# Sitara_IO_Bank_123.net
KiCad netlist of a schematic drawn in Altium Designer
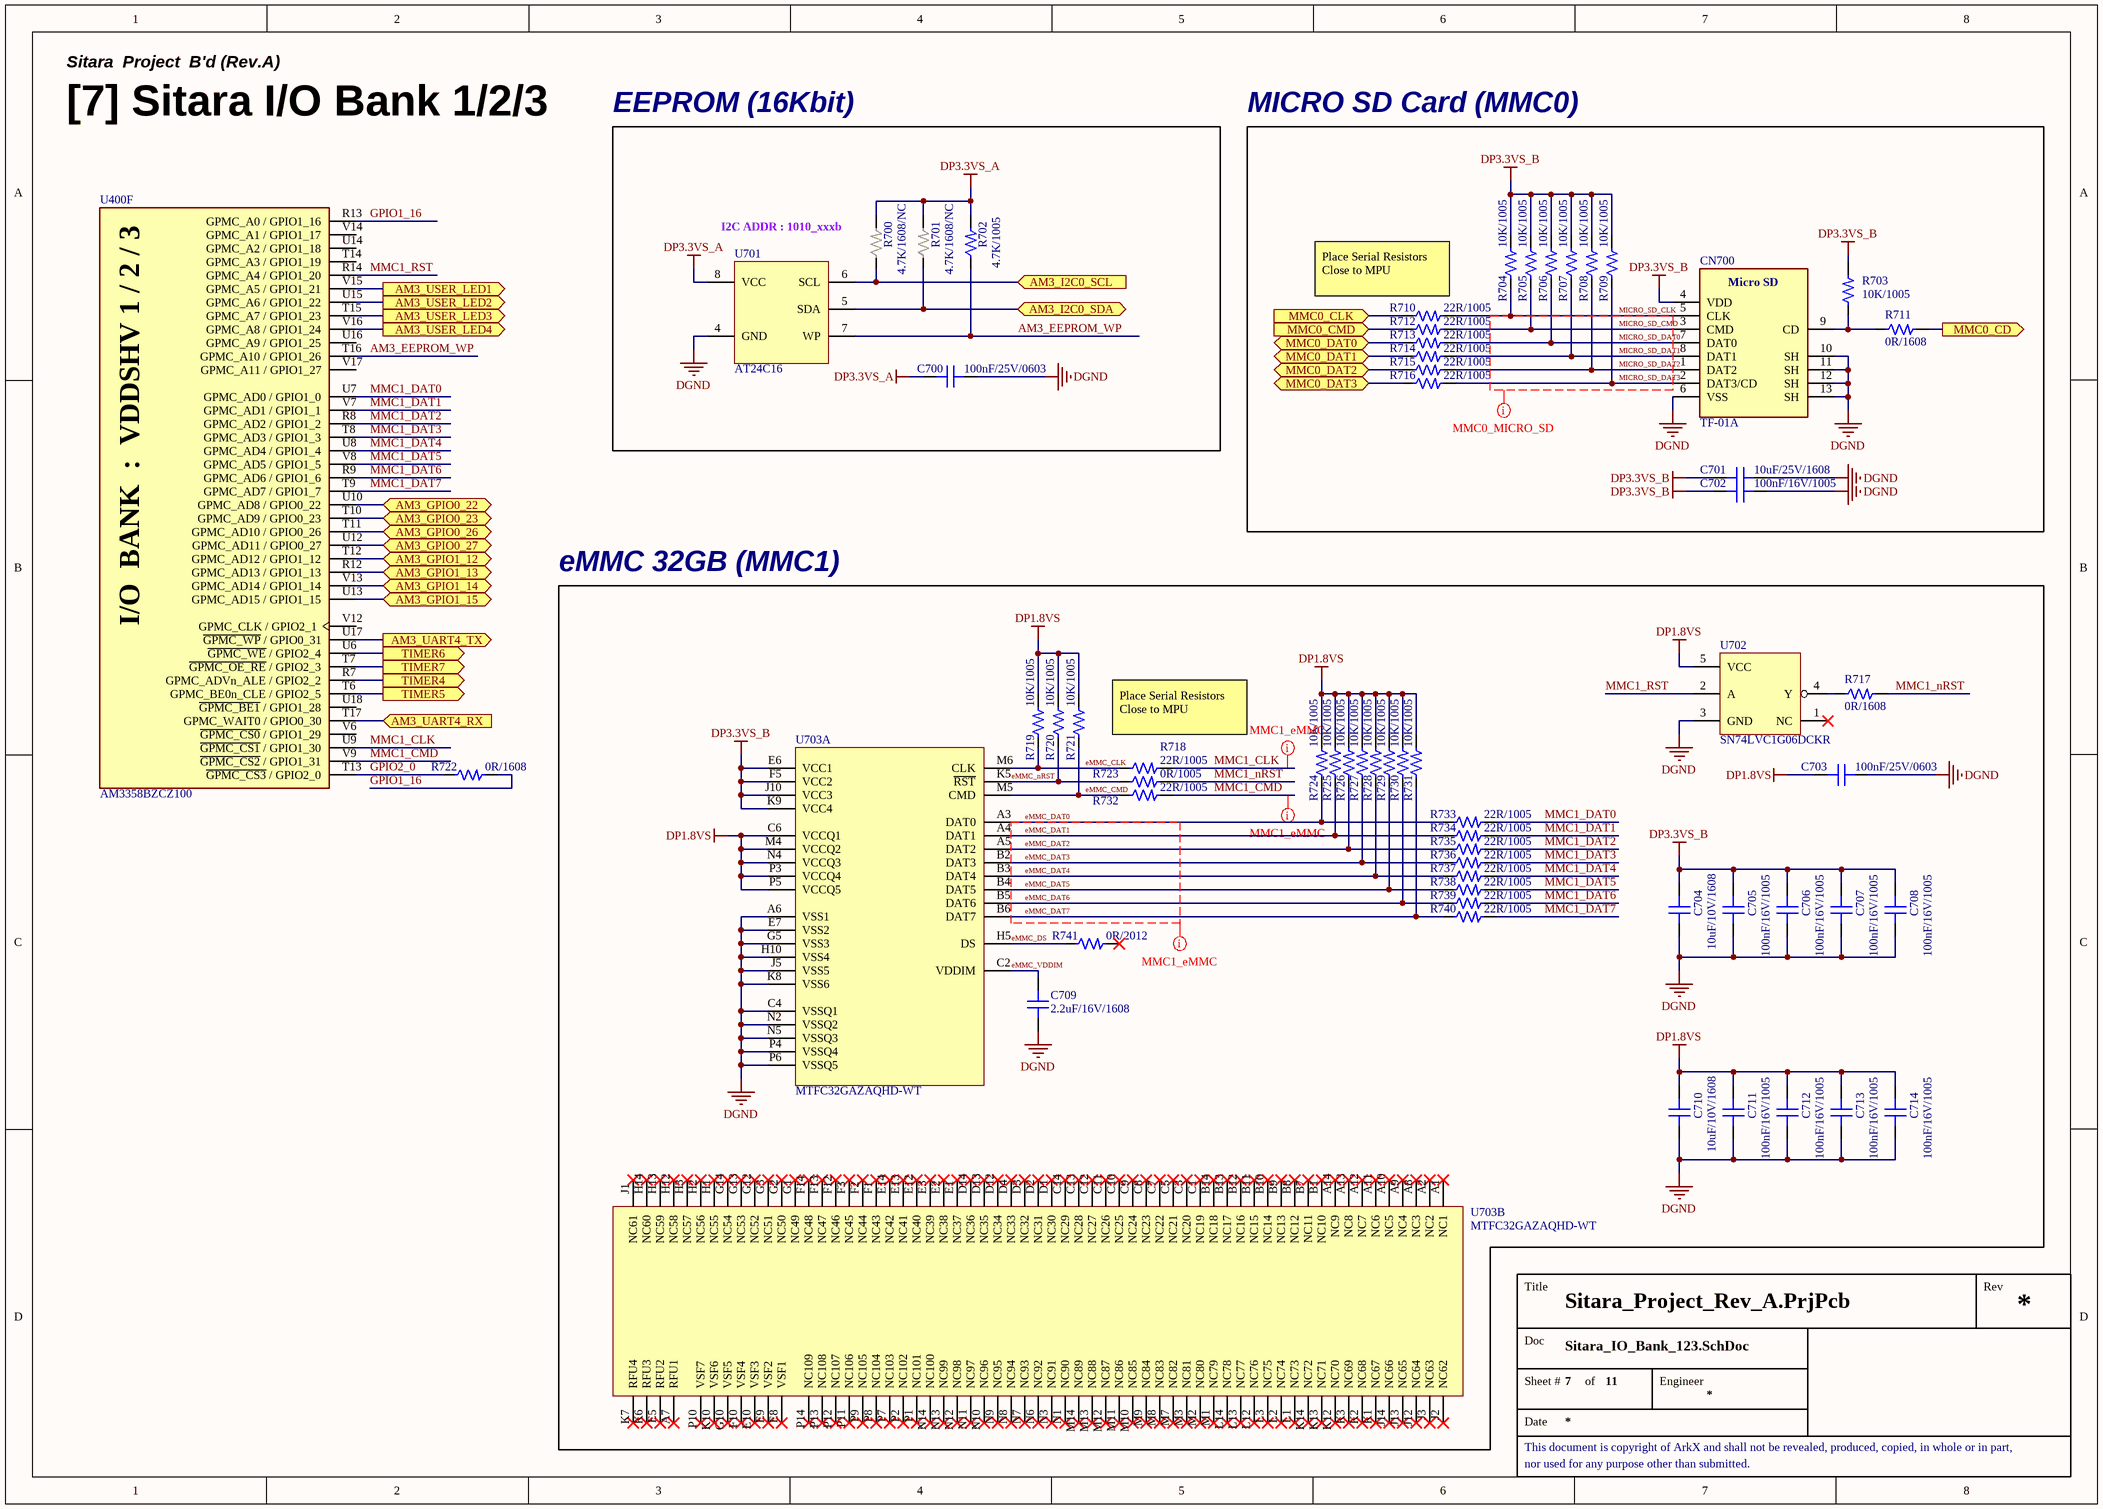
[diagram p0: Sitara_IO_Bank_123.SchDoc]

(export (version "E")
  (design (tool "Eeschema 10.0.6"))
  (components
    (comp (ref "C700")
      (value "100nF/25V/0603")
      (footprint "CAP 0603 (0201_INCH)")
      (description "Ceramic CAP_100nF/25V/0603")
      (fields (field (name "LCSC PART #") "C181047"))
      (libsource (lib "Arkx") (part "CAP_100nF/25V/0603"))
    )
    (comp (ref "C701")
      (value "10uF/25V/1608")
      (footprint "CAP 1608 (0603_INCH)")
      (description "Ceramic CAP_10uF/25V/1608")
      (fields (field (name "LCSC PART #") "C96446"))
      (libsource (lib "Arkx") (part "CAP_10uF/25V/1608"))
    )
    (comp (ref "C702")
      (value "100nF/16V/1005")
      (footprint "CAP 1005 (0402_INCH)")
      (description "Ceramic CAP_100nF/16V/1005")
      (fields (field (name "LCSC PART #") "C1525"))
      (libsource (lib "Arkx") (part "CAP_100nF/16V/1005"))
    )
    (comp (ref "C703")
      (value "100nF/25V/0603")
      (footprint "CAP 0603 (0201_INCH)")
      (description "Ceramic CAP_100nF/25V/0603")
      (fields (field (name "LCSC PART #") "C181047"))
      (libsource (lib "Arkx") (part "CAP_100nF/25V/0603"))
    )
    (comp (ref "C704")
      (value "10uF/10V/1608")
      (footprint "CAP 1608 (0603_INCH)")
      (description "Ceramic CAP_10uF/10V/1608")
      (fields (field (name "LCSC PART #") "C19702"))
      (libsource (lib "Arkx") (part "CAP_10uF/10V/1608"))
    )
    (comp (ref "C705")
      (value "100nF/16V/1005")
      (footprint "CAP 1005 (0402_INCH)")
      (description "Ceramic CAP_100nF/16V/1005")
      (fields (field (name "LCSC PART #") "C1525"))
      (libsource (lib "Arkx") (part "CAP_100nF/16V/1005"))
    )
    (comp (ref "C706")
      (value "100nF/16V/1005")
      (footprint "CAP 1005 (0402_INCH)")
      (description "Ceramic CAP_100nF/16V/1005")
      (fields (field (name "LCSC PART #") "C1525"))
      (libsource (lib "Arkx") (part "CAP_100nF/16V/1005"))
    )
    (comp (ref "C707")
      (value "100nF/16V/1005")
      (footprint "CAP 1005 (0402_INCH)")
      (description "Ceramic CAP_100nF/16V/1005")
      (fields (field (name "LCSC PART #") "C1525"))
      (libsource (lib "Arkx") (part "CAP_100nF/16V/1005"))
    )
    (comp (ref "C708")
      (value "100nF/16V/1005")
      (footprint "CAP 1005 (0402_INCH)")
      (description "Ceramic CAP_100nF/16V/1005")
      (fields (field (name "LCSC PART #") "C1525"))
      (libsource (lib "Arkx") (part "CAP_100nF/16V/1005"))
    )
    (comp (ref "C709")
      (value "2.2uF/16V/1608")
      (footprint "CAP 1608 (0603_INCH)")
      (description "Ceramic CAP_2.2uF/16V/1608")
      (fields (field (name "LCSC PART #") "C23630"))
      (libsource (lib "Arkx") (part "CAP_2.2uF/16V/1608"))
    )
    (comp (ref "C710")
      (value "10uF/10V/1608")
      (footprint "CAP 1608 (0603_INCH)")
      (description "Ceramic CAP_10uF/10V/1608")
      (fields (field (name "LCSC PART #") "C19702"))
      (libsource (lib "Arkx") (part "CAP_10uF/10V/1608"))
    )
    (comp (ref "C711")
      (value "100nF/16V/1005")
      (footprint "CAP 1005 (0402_INCH)")
      (description "Ceramic CAP_100nF/16V/1005")
      (fields (field (name "LCSC PART #") "C1525"))
      (libsource (lib "Arkx") (part "CAP_100nF/16V/1005"))
    )
    (comp (ref "C712")
      (value "100nF/16V/1005")
      (footprint "CAP 1005 (0402_INCH)")
      (description "Ceramic CAP_100nF/16V/1005")
      (fields (field (name "LCSC PART #") "C1525"))
      (libsource (lib "Arkx") (part "CAP_100nF/16V/1005"))
    )
    (comp (ref "C713")
      (value "100nF/16V/1005")
      (footprint "CAP 1005 (0402_INCH)")
      (description "Ceramic CAP_100nF/16V/1005")
      (fields (field (name "LCSC PART #") "C1525"))
      (libsource (lib "Arkx") (part "CAP_100nF/16V/1005"))
    )
    (comp (ref "C714")
      (value "100nF/16V/1005")
      (footprint "CAP 1005 (0402_INCH)")
      (description "Ceramic CAP_100nF/16V/1005")
      (fields (field (name "LCSC PART #") "C1525"))
      (libsource (lib "Arkx") (part "CAP_100nF/16V/1005"))
    )
    (comp (ref "CN700")
      (value "TF-01A")
      (footprint "CON_MICRO-SD_Socket_TF-01A")
      (description "Card Slot MicroSD card (TF card) Self-bouncing SMD SD Card / Memory Card Connector ROHS")
      (fields (field (name "LCSC PART #") "C91145"))
      (libsource (lib "Arkx") (part "CON_MICRO-SD_Socket_TF-01A"))
    )
    (comp (ref "R700")
      (value "4.7K/1608/NC")
      (footprint "RES 1608 (0603_inch)/NC")
      (description "RES_4.7K/1608/0.1W")
      (libsource (lib "Arkx") (part "RES_NC_4.7K/1608/0.1W"))
    )
    (comp (ref "R701")
      (value "4.7K/1608/NC")
      (footprint "RES 1608 (0603_inch)/NC")
      (description "RES_4.7K/1608/0.1W")
      (libsource (lib "Arkx") (part "RES_NC_4.7K/1608/0.1W"))
    )
    (comp (ref "R702")
      (value "4.7K/1005")
      (footprint "RES 1005 (0402_inch)")
      (description "RES_4.7K/1005/62.5mW")
      (fields (field (name "LCSC PART #") "C25900"))
      (libsource (lib "Arkx") (part "RES_4.7K/1005/62.5mW"))
    )
    (comp (ref "R703")
      (value "10K/1005")
      (footprint "RES 1005 (0402_inch)")
      (description "RES_10K/1005/62.5mW")
      (fields (field (name "LCSC PART #") "C25744"))
      (libsource (lib "Arkx") (part "RES_10K/1005/62.5mW"))
    )
    (comp (ref "R704")
      (value "10K/1005")
      (footprint "RES 1005 (0402_inch)")
      (description "RES_10K/1005/62.5mW")
      (fields (field (name "LCSC PART #") "C25744"))
      (libsource (lib "Arkx") (part "RES_10K/1005/62.5mW"))
    )
    (comp (ref "R705")
      (value "10K/1005")
      (footprint "RES 1005 (0402_inch)")
      (description "RES_10K/1005/62.5mW")
      (fields (field (name "LCSC PART #") "C25744"))
      (libsource (lib "Arkx") (part "RES_10K/1005/62.5mW"))
    )
    (comp (ref "R706")
      (value "10K/1005")
      (footprint "RES 1005 (0402_inch)")
      (description "RES_10K/1005/62.5mW")
      (fields (field (name "LCSC PART #") "C25744"))
      (libsource (lib "Arkx") (part "RES_10K/1005/62.5mW"))
    )
    (comp (ref "R707")
      (value "10K/1005")
      (footprint "RES 1005 (0402_inch)")
      (description "RES_10K/1005/62.5mW")
      (fields (field (name "LCSC PART #") "C25744"))
      (libsource (lib "Arkx") (part "RES_10K/1005/62.5mW"))
    )
    (comp (ref "R708")
      (value "10K/1005")
      (footprint "RES 1005 (0402_inch)")
      (description "RES_10K/1005/62.5mW")
      (fields (field (name "LCSC PART #") "C25744"))
      (libsource (lib "Arkx") (part "RES_10K/1005/62.5mW"))
    )
    (comp (ref "R709")
      (value "10K/1005")
      (footprint "RES 1005 (0402_inch)")
      (description "RES_10K/1005/62.5mW")
      (fields (field (name "LCSC PART #") "C25744"))
      (libsource (lib "Arkx") (part "RES_10K/1005/62.5mW"))
    )
    (comp (ref "R710")
      (value "22R/1005")
      (footprint "RES 1005 (0402_inch)")
      (description "RES_22R/1005/62.5mW")
      (fields (field (name "LCSC PART #") "C25092"))
      (libsource (lib "Arkx") (part "RES_22R/1005/62.5mW"))
    )
    (comp (ref "R711")
      (value "0R/1608")
      (footprint "RES 1608 (0603_inch)")
      (description "RES_0R/1608/0.1W")
      (fields (field (name "LCSC PART #") "C21189"))
      (libsource (lib "Arkx") (part "RES_0R/1608/0.1W"))
    )
    (comp (ref "R712")
      (value "22R/1005")
      (footprint "RES 1005 (0402_inch)")
      (description "RES_22R/1005/62.5mW")
      (fields (field (name "LCSC PART #") "C25092"))
      (libsource (lib "Arkx") (part "RES_22R/1005/62.5mW"))
    )
    (comp (ref "R713")
      (value "22R/1005")
      (footprint "RES 1005 (0402_inch)")
      (description "RES_22R/1005/62.5mW")
      (fields (field (name "LCSC PART #") "C25092"))
      (libsource (lib "Arkx") (part "RES_22R/1005/62.5mW"))
    )
    (comp (ref "R714")
      (value "22R/1005")
      (footprint "RES 1005 (0402_inch)")
      (description "RES_22R/1005/62.5mW")
      (fields (field (name "LCSC PART #") "C25092"))
      (libsource (lib "Arkx") (part "RES_22R/1005/62.5mW"))
    )
    (comp (ref "R715")
      (value "22R/1005")
      (footprint "RES 1005 (0402_inch)")
      (description "RES_22R/1005/62.5mW")
      (fields (field (name "LCSC PART #") "C25092"))
      (libsource (lib "Arkx") (part "RES_22R/1005/62.5mW"))
    )
    (comp (ref "R716")
      (value "22R/1005")
      (footprint "RES 1005 (0402_inch)")
      (description "RES_22R/1005/62.5mW")
      (fields (field (name "LCSC PART #") "C25092"))
      (libsource (lib "Arkx") (part "RES_22R/1005/62.5mW"))
    )
    (comp (ref "R717")
      (value "0R/1608")
      (footprint "RES 1608 (0603_inch)")
      (description "RES_0R/1608/0.1W")
      (fields (field (name "LCSC PART #") "C21189"))
      (libsource (lib "Arkx") (part "RES_0R/1608/0.1W"))
    )
    (comp (ref "R718")
      (value "22R/1005")
      (footprint "RES 1005 (0402_inch)")
      (description "RES_22R/1005/62.5mW")
      (fields (field (name "LCSC PART #") "C25092"))
      (libsource (lib "Arkx") (part "RES_22R/1005/62.5mW"))
    )
    (comp (ref "R719")
      (value "10K/1005")
      (footprint "RES 1005 (0402_inch)")
      (description "RES_10K/1005/62.5mW")
      (fields (field (name "LCSC PART #") "C25744"))
      (libsource (lib "Arkx") (part "RES_10K/1005/62.5mW"))
    )
    (comp (ref "R720")
      (value "10K/1005")
      (footprint "RES 1005 (0402_inch)")
      (description "RES_10K/1005/62.5mW")
      (fields (field (name "LCSC PART #") "C25744"))
      (libsource (lib "Arkx") (part "RES_10K/1005/62.5mW"))
    )
    (comp (ref "R721")
      (value "10K/1005")
      (footprint "RES 1005 (0402_inch)")
      (description "RES_10K/1005/62.5mW")
      (fields (field (name "LCSC PART #") "C25744"))
      (libsource (lib "Arkx") (part "RES_10K/1005/62.5mW"))
    )
    (comp (ref "R722")
      (value "0R/1608")
      (footprint "RES 1608 (0603_inch)")
      (description "RES_0R/1608/0.1W")
      (fields (field (name "LCSC PART #") "C21189"))
      (libsource (lib "Arkx") (part "RES_0R/1608/0.1W"))
    )
    (comp (ref "R723")
      (value "0R/1005")
      (footprint "RES 1005 (0402_inch)")
      (description "RES_0R/1005/62.5mW")
      (fields (field (name "LCSC PART #") "C17168"))
      (libsource (lib "Arkx") (part "RES_0R/1005/62.5mW"))
    )
    (comp (ref "R724")
      (value "10K/1005")
      (footprint "RES 1005 (0402_inch)")
      (description "RES_10K/1005/62.5mW")
      (fields (field (name "LCSC PART #") "C25744"))
      (libsource (lib "Arkx") (part "RES_10K/1005/62.5mW"))
    )
    (comp (ref "R725")
      (value "10K/1005")
      (footprint "RES 1005 (0402_inch)")
      (description "RES_10K/1005/62.5mW")
      (fields (field (name "LCSC PART #") "C25744"))
      (libsource (lib "Arkx") (part "RES_10K/1005/62.5mW"))
    )
    (comp (ref "R726")
      (value "10K/1005")
      (footprint "RES 1005 (0402_inch)")
      (description "RES_10K/1005/62.5mW")
      (fields (field (name "LCSC PART #") "C25744"))
      (libsource (lib "Arkx") (part "RES_10K/1005/62.5mW"))
    )
    (comp (ref "R727")
      (value "10K/1005")
      (footprint "RES 1005 (0402_inch)")
      (description "RES_10K/1005/62.5mW")
      (fields (field (name "LCSC PART #") "C25744"))
      (libsource (lib "Arkx") (part "RES_10K/1005/62.5mW"))
    )
    (comp (ref "R728")
      (value "10K/1005")
      (footprint "RES 1005 (0402_inch)")
      (description "RES_10K/1005/62.5mW")
      (fields (field (name "LCSC PART #") "C25744"))
      (libsource (lib "Arkx") (part "RES_10K/1005/62.5mW"))
    )
    (comp (ref "R729")
      (value "10K/1005")
      (footprint "RES 1005 (0402_inch)")
      (description "RES_10K/1005/62.5mW")
      (fields (field (name "LCSC PART #") "C25744"))
      (libsource (lib "Arkx") (part "RES_10K/1005/62.5mW"))
    )
    (comp (ref "R730")
      (value "10K/1005")
      (footprint "RES 1005 (0402_inch)")
      (description "RES_10K/1005/62.5mW")
      (fields (field (name "LCSC PART #") "C25744"))
      (libsource (lib "Arkx") (part "RES_10K/1005/62.5mW"))
    )
    (comp (ref "R731")
      (value "10K/1005")
      (footprint "RES 1005 (0402_inch)")
      (description "RES_10K/1005/62.5mW")
      (fields (field (name "LCSC PART #") "C25744"))
      (libsource (lib "Arkx") (part "RES_10K/1005/62.5mW"))
    )
    (comp (ref "R732")
      (value "22R/1005")
      (footprint "RES 1005 (0402_inch)")
      (description "RES_22R/1005/62.5mW")
      (fields (field (name "LCSC PART #") "C25092"))
      (libsource (lib "Arkx") (part "RES_22R/1005/62.5mW"))
    )
    (comp (ref "R733")
      (value "22R/1005")
      (footprint "RES 1005 (0402_inch)")
      (description "RES_22R/1005/62.5mW")
      (fields (field (name "LCSC PART #") "C25092"))
      (libsource (lib "Arkx") (part "RES_22R/1005/62.5mW"))
    )
    (comp (ref "R734")
      (value "22R/1005")
      (footprint "RES 1005 (0402_inch)")
      (description "RES_22R/1005/62.5mW")
      (fields (field (name "LCSC PART #") "C25092"))
      (libsource (lib "Arkx") (part "RES_22R/1005/62.5mW"))
    )
    (comp (ref "R735")
      (value "22R/1005")
      (footprint "RES 1005 (0402_inch)")
      (description "RES_22R/1005/62.5mW")
      (fields (field (name "LCSC PART #") "C25092"))
      (libsource (lib "Arkx") (part "RES_22R/1005/62.5mW"))
    )
    (comp (ref "R736")
      (value "22R/1005")
      (footprint "RES 1005 (0402_inch)")
      (description "RES_22R/1005/62.5mW")
      (fields (field (name "LCSC PART #") "C25092"))
      (libsource (lib "Arkx") (part "RES_22R/1005/62.5mW"))
    )
    (comp (ref "R737")
      (value "22R/1005")
      (footprint "RES 1005 (0402_inch)")
      (description "RES_22R/1005/62.5mW")
      (fields (field (name "LCSC PART #") "C25092"))
      (libsource (lib "Arkx") (part "RES_22R/1005/62.5mW"))
    )
    (comp (ref "R738")
      (value "22R/1005")
      (footprint "RES 1005 (0402_inch)")
      (description "RES_22R/1005/62.5mW")
      (fields (field (name "LCSC PART #") "C25092"))
      (libsource (lib "Arkx") (part "RES_22R/1005/62.5mW"))
    )
    (comp (ref "R739")
      (value "22R/1005")
      (footprint "RES 1005 (0402_inch)")
      (description "RES_22R/1005/62.5mW")
      (fields (field (name "LCSC PART #") "C25092"))
      (libsource (lib "Arkx") (part "RES_22R/1005/62.5mW"))
    )
    (comp (ref "R740")
      (value "22R/1005")
      (footprint "RES 1005 (0402_inch)")
      (description "RES_22R/1005/62.5mW")
      (fields (field (name "LCSC PART #") "C25092"))
      (libsource (lib "Arkx") (part "RES_22R/1005/62.5mW"))
    )
    (comp (ref "R741")
      (value "0R/2012")
      (footprint "RES 2012 (0805_inch)")
      (description "RES_0R/2012/0.125W")
      (fields (field (name "LCSC PART #") "C17477"))
      (libsource (lib "Arkx") (part "RES_0R/2012/0.125W"))
    )
    (comp (ref "U400")
      (value "AM3358BZCZ100")
      (footprint "IC_SOC_AM3358BZCZ100")
      (description "ARM® Cortex®-A8 Microprocessor IC Sitara™ 1 Core, 32-Bit 1.0GHz 324-NFBGA (15x15)")
      (fields (field (name "LCSC PART #") "C73932"))
      (libsource (lib "Arkx") (part "IC_SOC_AM3358BZCZ100"))
    )
    (comp (ref "U701")
      (value "AT24C16")
      (footprint "TSSOP-8_PW (TI)")
      (description "IC EEPROM 16KBIT I2C 1MHZ 8TSSOP")
      (fields (field (name "LCSC PART #") "C112954"))
      (libsource (lib "Arkx") (part "IC_EEPROM_AT24C16"))
    )
    (comp (ref "U702")
      (value "SN74LVC1G06DCKR")
      (footprint "IC_SC-70-5")
      (description "Inverter IC 1 Channel Open Drain SC-70-5")
      (fields (field (name "LCSC PART #") "C7828"))
      (libsource (lib "Arkx") (part "IC_BUF_SN74LVC1G06DCKR"))
    )
    (comp (ref "U703")
      (value "MTFC32GAZAQHD-WT")
      (footprint "IC_VFBGA-153")
      (description "FLASH - NAND Memory IC 256Gbit MMC 200 MHz 153-VFBGA (11.5x13)")
      (fields (field (name "LCSC PART #") "C5330430"))
      (libsource (lib "") (part "IC_eMMC_MTFC32GAZAQHD-WT_1"))
    )
  )
  (nets
    (net (code "1") (name "/AM3_EEPROM_WP") (class "Default")
      (node (ref "R702") (pin "1") (pinfunction "1_1") (pintype "passive"))
      (node (ref "U400") (pin "T16") (pinfunction "GPMC_A10_/_GPIO1_26_T16") (pintype "passive"))
      (node (ref "U701") (pin "7") (pinfunction "WP_7") (pintype "passive"))
    )
    (net (code "2") (name "/AM3_GPIO0_22") (class "Default")
      (node (ref "U400") (pin "U10") (pinfunction "GPMC_AD8_/_GPIO0_22_U10") (pintype "passive"))
    )
    (net (code "3") (name "/AM3_GPIO0_23") (class "Default")
      (node (ref "U400") (pin "T10") (pinfunction "GPMC_AD9_/_GPIO0_23_T10") (pintype "passive"))
    )
    (net (code "4") (name "/AM3_GPIO0_26") (class "Default")
      (node (ref "U400") (pin "T11") (pinfunction "GPMC_AD10_/_GPIO0_26_T11") (pintype "passive"))
    )
    (net (code "5") (name "/AM3_GPIO0_27") (class "Default")
      (node (ref "U400") (pin "U12") (pinfunction "GPMC_AD11_/_GPIO0_27_U12") (pintype "passive"))
    )
    (net (code "6") (name "/AM3_GPIO1_12") (class "Default")
      (node (ref "U400") (pin "T12") (pinfunction "GPMC_AD12_/_GPIO1_12_T12") (pintype "passive"))
    )
    (net (code "7") (name "/AM3_GPIO1_13") (class "Default")
      (node (ref "U400") (pin "R12") (pinfunction "GPMC_AD13_/_GPIO1_13_R12") (pintype "passive"))
    )
    (net (code "8") (name "/AM3_GPIO1_14") (class "Default")
      (node (ref "U400") (pin "V13") (pinfunction "GPMC_AD14_/_GPIO1_14_V13") (pintype "passive"))
    )
    (net (code "9") (name "/AM3_GPIO1_15") (class "Default")
      (node (ref "U400") (pin "U13") (pinfunction "GPMC_AD15_/_GPIO1_15_U13") (pintype "passive"))
    )
    (net (code "10") (name "/AM3_I2C0_SCL") (class "Default")
      (node (ref "R700") (pin "1") (pinfunction "1_1") (pintype "passive"))
      (node (ref "U701") (pin "6") (pinfunction "SCL_6") (pintype "passive"))
    )
    (net (code "11") (name "/AM3_I2C0_SDA") (class "Default")
      (node (ref "R701") (pin "1") (pinfunction "1_1") (pintype "passive"))
      (node (ref "U701") (pin "5") (pinfunction "SDA_5") (pintype "passive"))
    )
    (net (code "12") (name "/AM3_UART4_RX") (class "Default")
      (node (ref "U400") (pin "T17") (pinfunction "GPMC_WAIT0_/_GPIO0_30_T17") (pintype "passive"))
    )
    (net (code "13") (name "/AM3_UART4_TX") (class "Default")
      (node (ref "U400") (pin "U17") (pinfunction "~{GPMC_WP}_/_GPIO0_31_U17") (pintype "passive"))
    )
    (net (code "14") (name "/AM3_USER_LED1") (class "Default")
      (node (ref "U400") (pin "V15") (pinfunction "GPMC_A5_/_GPIO1_21_V15") (pintype "passive"))
    )
    (net (code "15") (name "/AM3_USER_LED2") (class "Default")
      (node (ref "U400") (pin "U15") (pinfunction "GPMC_A6_/_GPIO1_22_U15") (pintype "passive"))
    )
    (net (code "16") (name "/AM3_USER_LED3") (class "Default")
      (node (ref "U400") (pin "T15") (pinfunction "GPMC_A7_/_GPIO1_23_T15") (pintype "passive"))
    )
    (net (code "17") (name "/AM3_USER_LED4") (class "Default")
      (node (ref "U400") (pin "V16") (pinfunction "GPMC_A8_/_GPIO1_24_V16") (pintype "passive"))
    )
    (net (code "18") (name "/GPIO1_16") (class "Default")
      (node (ref "R722") (pin "2") (pinfunction "2_2") (pintype "passive"))
      (node (ref "U400") (pin "R13") (pinfunction "GPMC_A0_/_GPIO1_16_R13") (pintype "passive"))
    )
    (net (code "19") (name "/GPIO2_0") (class "Default")
      (node (ref "R722") (pin "1") (pinfunction "1_1") (pintype "passive"))
      (node (ref "U400") (pin "T13") (pinfunction "~{GPMC_CS3}_/_GPIO2_0_T13") (pintype "passive"))
    )
    (net (code "20") (name "/MICRO_SD_CLK") (class "Default")
      (node (ref "CN700") (pin "5") (pinfunction "CLK_5") (pintype "passive"))
      (node (ref "R704") (pin "1") (pinfunction "1_1") (pintype "passive"))
      (node (ref "R710") (pin "2") (pinfunction "2_2") (pintype "passive"))
    )
    (net (code "21") (name "/MICRO_SD_CMD") (class "Default")
      (node (ref "CN700") (pin "3") (pinfunction "CMD_3") (pintype "passive"))
      (node (ref "R705") (pin "1") (pinfunction "1_1") (pintype "passive"))
      (node (ref "R712") (pin "2") (pinfunction "2_2") (pintype "passive"))
    )
    (net (code "22") (name "/MICRO_SD_DAT0") (class "Default")
      (node (ref "CN700") (pin "7") (pinfunction "DAT0_7") (pintype "passive"))
      (node (ref "R706") (pin "1") (pinfunction "1_1") (pintype "passive"))
      (node (ref "R713") (pin "2") (pinfunction "2_2") (pintype "passive"))
    )
    (net (code "23") (name "/MICRO_SD_DAT1") (class "Default")
      (node (ref "CN700") (pin "8") (pinfunction "DAT1_8") (pintype "passive"))
      (node (ref "R707") (pin "1") (pinfunction "1_1") (pintype "passive"))
      (node (ref "R714") (pin "2") (pinfunction "2_2") (pintype "passive"))
    )
    (net (code "24") (name "/MICRO_SD_DAT2") (class "Default")
      (node (ref "CN700") (pin "1") (pinfunction "DAT2_1") (pintype "passive"))
      (node (ref "R708") (pin "1") (pinfunction "1_1") (pintype "passive"))
      (node (ref "R715") (pin "2") (pinfunction "2_2") (pintype "passive"))
    )
    (net (code "25") (name "/MICRO_SD_DAT3") (class "Default")
      (node (ref "CN700") (pin "2") (pinfunction "DAT3/CD_2") (pintype "passive"))
      (node (ref "R709") (pin "1") (pinfunction "1_1") (pintype "passive"))
      (node (ref "R716") (pin "2") (pinfunction "2_2") (pintype "passive"))
    )
    (net (code "26") (name "/MMC0_CD") (class "Default")
      (node (ref "R711") (pin "2") (pinfunction "2_2") (pintype "passive"))
    )
    (net (code "27") (name "/MMC0_CLK") (class "Default")
      (node (ref "R710") (pin "1") (pinfunction "1_1") (pintype "passive"))
    )
    (net (code "28") (name "/MMC0_CMD") (class "Default")
      (node (ref "R712") (pin "1") (pinfunction "1_1") (pintype "passive"))
    )
    (net (code "29") (name "/MMC0_DAT0") (class "Default")
      (node (ref "R713") (pin "1") (pinfunction "1_1") (pintype "passive"))
    )
    (net (code "30") (name "/MMC0_DAT1") (class "Default")
      (node (ref "R714") (pin "1") (pinfunction "1_1") (pintype "passive"))
    )
    (net (code "31") (name "/MMC0_DAT2") (class "Default")
      (node (ref "R715") (pin "1") (pinfunction "1_1") (pintype "passive"))
    )
    (net (code "32") (name "/MMC0_DAT3") (class "Default")
      (node (ref "R716") (pin "1") (pinfunction "1_1") (pintype "passive"))
    )
    (net (code "33") (name "/MMC1_CLK") (class "Default")
      (node (ref "R718") (pin "2") (pinfunction "2_2") (pintype "passive"))
      (node (ref "U400") (pin "U9") (pinfunction "~{GPMC_CS1}_/_GPIO1_30_U9") (pintype "passive"))
    )
    (net (code "34") (name "/MMC1_CMD") (class "Default")
      (node (ref "R732") (pin "2") (pinfunction "2_2") (pintype "passive"))
      (node (ref "U400") (pin "V9") (pinfunction "~{GPMC_CS2}_/_GPIO1_31_V9") (pintype "passive"))
    )
    (net (code "35") (name "/MMC1_DAT0") (class "Default")
      (node (ref "R733") (pin "2") (pinfunction "2_2") (pintype "passive"))
      (node (ref "U400") (pin "U7") (pinfunction "GPMC_AD0_/_GPIO1_0_U7") (pintype "passive"))
    )
    (net (code "36") (name "/MMC1_DAT1") (class "Default")
      (node (ref "R734") (pin "2") (pinfunction "2_2") (pintype "passive"))
      (node (ref "U400") (pin "V7") (pinfunction "GPMC_AD1_/_GPIO1_1_V7") (pintype "passive"))
    )
    (net (code "37") (name "/MMC1_DAT2") (class "Default")
      (node (ref "R735") (pin "2") (pinfunction "2_2") (pintype "passive"))
      (node (ref "U400") (pin "R8") (pinfunction "GPMC_AD2_/_GPIO1_2_R8") (pintype "passive"))
    )
    (net (code "38") (name "/MMC1_DAT3") (class "Default")
      (node (ref "R736") (pin "2") (pinfunction "2_2") (pintype "passive"))
      (node (ref "U400") (pin "T8") (pinfunction "GPMC_AD3_/_GPIO1_3_T8") (pintype "passive"))
    )
    (net (code "39") (name "/MMC1_DAT4") (class "Default")
      (node (ref "R737") (pin "2") (pinfunction "2_2") (pintype "passive"))
      (node (ref "U400") (pin "U8") (pinfunction "GPMC_AD4_/_GPIO1_4_U8") (pintype "passive"))
    )
    (net (code "40") (name "/MMC1_DAT5") (class "Default")
      (node (ref "R738") (pin "2") (pinfunction "2_2") (pintype "passive"))
      (node (ref "U400") (pin "V8") (pinfunction "GPMC_AD5_/_GPIO1_5_V8") (pintype "passive"))
    )
    (net (code "41") (name "/MMC1_DAT6") (class "Default")
      (node (ref "R739") (pin "2") (pinfunction "2_2") (pintype "passive"))
      (node (ref "U400") (pin "R9") (pinfunction "GPMC_AD6_/_GPIO1_6_R9") (pintype "passive"))
    )
    (net (code "42") (name "/MMC1_DAT7") (class "Default")
      (node (ref "R740") (pin "2") (pinfunction "2_2") (pintype "passive"))
      (node (ref "U400") (pin "T9") (pinfunction "GPMC_AD7_/_GPIO1_7_T9") (pintype "passive"))
    )
    (net (code "43") (name "/MMC1_RST") (class "Default")
      (node (ref "U400") (pin "R14") (pinfunction "GPMC_A4_/_GPIO1_20_R14") (pintype "passive"))
      (node (ref "U702") (pin "2") (pinfunction "A_2") (pintype "passive"))
    )
    (net (code "44") (name "/MMC1_nRST") (class "Default")
      (node (ref "R717") (pin "2") (pinfunction "2_2") (pintype "passive"))
      (node (ref "R723") (pin "2") (pinfunction "2_2") (pintype "passive"))
    )
    (net (code "45") (name "/TIMER4") (class "Default")
      (node (ref "U400") (pin "R7") (pinfunction "GPMC_ADVn_ALE_/_GPIO2_2_R7") (pintype "passive"))
    )
    (net (code "46") (name "/TIMER5") (class "Default")
      (node (ref "U400") (pin "T6") (pinfunction "GPMC_BE0n_CLE_/_GPIO2_5_T6") (pintype "passive"))
    )
    (net (code "47") (name "/TIMER6") (class "Default")
      (node (ref "U400") (pin "U6") (pinfunction "~{GPMC_WE}_/_GPIO2_4_U6") (pintype "passive"))
    )
    (net (code "48") (name "/TIMER7") (class "Default")
      (node (ref "U400") (pin "T7") (pinfunction "~{GPMC_OE_RE}_/_GPIO2_3_T7") (pintype "passive"))
    )
    (net (code "49") (name "/eMMC_CLK") (class "Default")
      (node (ref "R718") (pin "1") (pinfunction "1_1") (pintype "passive"))
      (node (ref "R719") (pin "1") (pinfunction "1_1") (pintype "passive"))
      (node (ref "U703") (pin "M6") (pinfunction "CLK_M6") (pintype "passive"))
    )
    (net (code "50") (name "/eMMC_CMD") (class "Default")
      (node (ref "R721") (pin "1") (pinfunction "1_1") (pintype "passive"))
      (node (ref "R732") (pin "1") (pinfunction "1_1") (pintype "passive"))
      (node (ref "U703") (pin "M5") (pinfunction "CMD_M5") (pintype "passive"))
    )
    (net (code "51") (name "/eMMC_DAT0") (class "Default")
      (node (ref "R724") (pin "1") (pinfunction "1_1") (pintype "passive"))
      (node (ref "R733") (pin "1") (pinfunction "1_1") (pintype "passive"))
      (node (ref "U703") (pin "A3") (pinfunction "DAT0_A3") (pintype "passive"))
    )
    (net (code "52") (name "/eMMC_DAT1") (class "Default")
      (node (ref "R725") (pin "1") (pinfunction "1_1") (pintype "passive"))
      (node (ref "R734") (pin "1") (pinfunction "1_1") (pintype "passive"))
      (node (ref "U703") (pin "A4") (pinfunction "DAT1_A4") (pintype "passive"))
    )
    (net (code "53") (name "/eMMC_DAT2") (class "Default")
      (node (ref "R726") (pin "1") (pinfunction "1_1") (pintype "passive"))
      (node (ref "R735") (pin "1") (pinfunction "1_1") (pintype "passive"))
      (node (ref "U703") (pin "A5") (pinfunction "DAT2_A5") (pintype "passive"))
    )
    (net (code "54") (name "/eMMC_DAT3") (class "Default")
      (node (ref "R727") (pin "1") (pinfunction "1_1") (pintype "passive"))
      (node (ref "R736") (pin "1") (pinfunction "1_1") (pintype "passive"))
      (node (ref "U703") (pin "B2") (pinfunction "DAT3_B2") (pintype "passive"))
    )
    (net (code "55") (name "/eMMC_DAT4") (class "Default")
      (node (ref "R728") (pin "1") (pinfunction "1_1") (pintype "passive"))
      (node (ref "R737") (pin "1") (pinfunction "1_1") (pintype "passive"))
      (node (ref "U703") (pin "B3") (pinfunction "DAT4_B3") (pintype "passive"))
    )
    (net (code "56") (name "/eMMC_DAT5") (class "Default")
      (node (ref "R729") (pin "1") (pinfunction "1_1") (pintype "passive"))
      (node (ref "R738") (pin "1") (pinfunction "1_1") (pintype "passive"))
      (node (ref "U703") (pin "B4") (pinfunction "DAT5_B4") (pintype "passive"))
    )
    (net (code "57") (name "/eMMC_DAT6") (class "Default")
      (node (ref "R730") (pin "1") (pinfunction "1_1") (pintype "passive"))
      (node (ref "R739") (pin "1") (pinfunction "1_1") (pintype "passive"))
      (node (ref "U703") (pin "B5") (pinfunction "DAT6_B5") (pintype "passive"))
    )
    (net (code "58") (name "/eMMC_DAT7") (class "Default")
      (node (ref "R731") (pin "1") (pinfunction "1_1") (pintype "passive"))
      (node (ref "R740") (pin "1") (pinfunction "1_1") (pintype "passive"))
      (node (ref "U703") (pin "B6") (pinfunction "DAT7_B6") (pintype "passive"))
    )
    (net (code "59") (name "/eMMC_DS") (class "Default")
      (node (ref "R741") (pin "1") (pinfunction "1_1") (pintype "passive"))
      (node (ref "U703") (pin "H5") (pinfunction "DS_H5") (pintype "passive"))
    )
    (net (code "60") (name "/eMMC_VDDIM") (class "Default")
      (node (ref "C709") (pin "2") (pinfunction "2_2") (pintype "passive"))
      (node (ref "U703") (pin "C2") (pinfunction "VDDIM_C2") (pintype "passive"))
    )
    (net (code "61") (name "/eMMC_nRST") (class "Default")
      (node (ref "R720") (pin "1") (pinfunction "1_1") (pintype "passive"))
      (node (ref "R723") (pin "1") (pinfunction "1_1") (pintype "passive"))
      (node (ref "U703") (pin "K5") (pinfunction "~{RST}_K5") (pintype "passive"))
    )
    (net (code "62") (name "DGND") (class "Default")
      (node (ref "C700") (pin "2") (pinfunction "2_2") (pintype "passive"))
      (node (ref "C701") (pin "2") (pinfunction "2_2") (pintype "passive"))
      (node (ref "C702") (pin "1") (pinfunction "1_1") (pintype "passive"))
      (node (ref "C703") (pin "1") (pinfunction "1_1") (pintype "passive"))
      (node (ref "C704") (pin "1") (pinfunction "1_1") (pintype "passive"))
      (node (ref "C705") (pin "1") (pinfunction "1_1") (pintype "passive"))
      (node (ref "C706") (pin "1") (pinfunction "1_1") (pintype "passive"))
      (node (ref "C707") (pin "1") (pinfunction "1_1") (pintype "passive"))
      (node (ref "C708") (pin "1") (pinfunction "1_1") (pintype "passive"))
      (node (ref "C709") (pin "1") (pinfunction "1_1") (pintype "passive"))
      (node (ref "C710") (pin "1") (pinfunction "1_1") (pintype "passive"))
      (node (ref "C711") (pin "1") (pinfunction "1_1") (pintype "passive"))
      (node (ref "C712") (pin "1") (pinfunction "1_1") (pintype "passive"))
      (node (ref "C713") (pin "1") (pinfunction "1_1") (pintype "passive"))
      (node (ref "C714") (pin "1") (pinfunction "1_1") (pintype "passive"))
      (node (ref "CN700") (pin "10") (pinfunction "SH_10") (pintype "passive"))
      (node (ref "CN700") (pin "11") (pinfunction "SH_11") (pintype "passive"))
      (node (ref "CN700") (pin "12") (pinfunction "SH_12") (pintype "passive"))
      (node (ref "CN700") (pin "13") (pinfunction "SH_13") (pintype "passive"))
      (node (ref "CN700") (pin "6") (pinfunction "VSS_6") (pintype "passive"))
      (node (ref "U701") (pin "4") (pinfunction "GND_4") (pintype "passive"))
      (node (ref "U702") (pin "3") (pinfunction "GND_3") (pintype "passive"))
      (node (ref "U703") (pin "A6") (pinfunction "VSS1_A6") (pintype "passive"))
      (node (ref "U703") (pin "C4") (pinfunction "VSSQ1_C4") (pintype "passive"))
      (node (ref "U703") (pin "E7") (pinfunction "VSS2_E7") (pintype "passive"))
      (node (ref "U703") (pin "G5") (pinfunction "VSS3_G5") (pintype "passive"))
      (node (ref "U703") (pin "H10") (pinfunction "VSS4_H10") (pintype "passive"))
      (node (ref "U703") (pin "J5") (pinfunction "VSS5_J5") (pintype "passive"))
      (node (ref "U703") (pin "K8") (pinfunction "VSS6_K8") (pintype "passive"))
      (node (ref "U703") (pin "N2") (pinfunction "VSSQ2_N2") (pintype "passive"))
      (node (ref "U703") (pin "N5") (pinfunction "VSSQ3_N5") (pintype "passive"))
      (node (ref "U703") (pin "P4") (pinfunction "VSSQ4_P4") (pintype "passive"))
      (node (ref "U703") (pin "P6") (pinfunction "VSSQ5_P6") (pintype "passive"))
    )
    (net (code "63") (name "DP1.8VS") (class "Default")
      (node (ref "C703") (pin "2") (pinfunction "2_2") (pintype "passive"))
      (node (ref "C710") (pin "2") (pinfunction "2_2") (pintype "passive"))
      (node (ref "C711") (pin "2") (pinfunction "2_2") (pintype "passive"))
      (node (ref "C712") (pin "2") (pinfunction "2_2") (pintype "passive"))
      (node (ref "C713") (pin "2") (pinfunction "2_2") (pintype "passive"))
      (node (ref "C714") (pin "2") (pinfunction "2_2") (pintype "passive"))
      (node (ref "R719") (pin "2") (pinfunction "2_2") (pintype "passive"))
      (node (ref "R720") (pin "2") (pinfunction "2_2") (pintype "passive"))
      (node (ref "R721") (pin "2") (pinfunction "2_2") (pintype "passive"))
      (node (ref "R724") (pin "2") (pinfunction "2_2") (pintype "passive"))
      (node (ref "R725") (pin "2") (pinfunction "2_2") (pintype "passive"))
      (node (ref "R726") (pin "2") (pinfunction "2_2") (pintype "passive"))
      (node (ref "R727") (pin "2") (pinfunction "2_2") (pintype "passive"))
      (node (ref "R728") (pin "2") (pinfunction "2_2") (pintype "passive"))
      (node (ref "R729") (pin "2") (pinfunction "2_2") (pintype "passive"))
      (node (ref "R730") (pin "2") (pinfunction "2_2") (pintype "passive"))
      (node (ref "R731") (pin "2") (pinfunction "2_2") (pintype "passive"))
      (node (ref "U702") (pin "5") (pinfunction "VCC_5") (pintype "passive"))
      (node (ref "U703") (pin "C6") (pinfunction "VCCQ1_C6") (pintype "passive"))
      (node (ref "U703") (pin "M4") (pinfunction "VCCQ2_M4") (pintype "passive"))
      (node (ref "U703") (pin "N4") (pinfunction "VCCQ3_N4") (pintype "passive"))
      (node (ref "U703") (pin "P3") (pinfunction "VCCQ4_P3") (pintype "passive"))
      (node (ref "U703") (pin "P5") (pinfunction "VCCQ5_P5") (pintype "passive"))
    )
    (net (code "64") (name "DP3.3VS_A") (class "Default")
      (node (ref "C700") (pin "1") (pinfunction "1_1") (pintype "passive"))
      (node (ref "R700") (pin "2") (pinfunction "2_2") (pintype "passive"))
      (node (ref "R701") (pin "2") (pinfunction "2_2") (pintype "passive"))
      (node (ref "R702") (pin "2") (pinfunction "2_2") (pintype "passive"))
      (node (ref "U701") (pin "8") (pinfunction "VCC_8") (pintype "passive"))
    )
    (net (code "65") (name "DP3.3VS_B") (class "Default")
      (node (ref "C701") (pin "1") (pinfunction "1_1") (pintype "passive"))
      (node (ref "C702") (pin "2") (pinfunction "2_2") (pintype "passive"))
      (node (ref "C704") (pin "2") (pinfunction "2_2") (pintype "passive"))
      (node (ref "C705") (pin "2") (pinfunction "2_2") (pintype "passive"))
      (node (ref "C706") (pin "2") (pinfunction "2_2") (pintype "passive"))
      (node (ref "C707") (pin "2") (pinfunction "2_2") (pintype "passive"))
      (node (ref "C708") (pin "2") (pinfunction "2_2") (pintype "passive"))
      (node (ref "CN700") (pin "4") (pinfunction "VDD_4") (pintype "passive"))
      (node (ref "R703") (pin "2") (pinfunction "2_2") (pintype "passive"))
      (node (ref "R704") (pin "2") (pinfunction "2_2") (pintype "passive"))
      (node (ref "R705") (pin "2") (pinfunction "2_2") (pintype "passive"))
      (node (ref "R706") (pin "2") (pinfunction "2_2") (pintype "passive"))
      (node (ref "R707") (pin "2") (pinfunction "2_2") (pintype "passive"))
      (node (ref "R708") (pin "2") (pinfunction "2_2") (pintype "passive"))
      (node (ref "R709") (pin "2") (pinfunction "2_2") (pintype "passive"))
      (node (ref "U703") (pin "E6") (pinfunction "VCC1_E6") (pintype "passive"))
      (node (ref "U703") (pin "F5") (pinfunction "VCC2_F5") (pintype "passive"))
      (node (ref "U703") (pin "J10") (pinfunction "VCC3_J10") (pintype "passive"))
      (node (ref "U703") (pin "K9") (pinfunction "VCC4_K9") (pintype "passive"))
    )
    (net (code "66") (name "Net-(CN700-CD)") (class "Default")
      (node (ref "CN700") (pin "9") (pinfunction "CD_9") (pintype "passive"))
      (node (ref "R703") (pin "1") (pinfunction "1_1") (pintype "passive"))
      (node (ref "R711") (pin "1") (pinfunction "1_1") (pintype "passive"))
    )
    (net (code "67") (name "Net-(U702-Y)") (class "Default")
      (node (ref "R717") (pin "1") (pinfunction "1_1") (pintype "passive"))
      (node (ref "U702") (pin "4") (pinfunction "Y_4") (pintype "passive"))
    )
    (net (code "68") (name "unconnected-(R741-Pad2)") (class "Default")
      (node (ref "R741") (pin "2") (pinfunction "2_2") (pintype "passive+no_connect"))
    )
    (net (code "69") (name "unconnected-(U400F-GPMC_A1_{slash}_GPIO1_17-PadV14)") (class "Default")
      (node (ref "U400") (pin "V14") (pinfunction "GPMC_A1_/_GPIO1_17_V14") (pintype "passive"))
    )
    (net (code "70") (name "unconnected-(U400F-GPMC_A2_{slash}_GPIO1_18-PadU14)") (class "Default")
      (node (ref "U400") (pin "U14") (pinfunction "GPMC_A2_/_GPIO1_18_U14") (pintype "passive"))
    )
    (net (code "71") (name "unconnected-(U400F-GPMC_A3_{slash}_GPIO1_19-PadT14)") (class "Default")
      (node (ref "U400") (pin "T14") (pinfunction "GPMC_A3_/_GPIO1_19_T14") (pintype "passive"))
    )
    (net (code "72") (name "unconnected-(U400F-GPMC_A9_{slash}_GPIO1_25-PadU16)") (class "Default")
      (node (ref "U400") (pin "U16") (pinfunction "GPMC_A9_/_GPIO1_25_U16") (pintype "passive"))
    )
    (net (code "73") (name "unconnected-(U400F-GPMC_A11_{slash}_GPIO1_27-PadV17)") (class "Default")
      (node (ref "U400") (pin "V17") (pinfunction "GPMC_A11_/_GPIO1_27_V17") (pintype "passive"))
    )
    (net (code "74") (name "unconnected-(U400F-GPMC_CLK_{slash}_GPIO2_1-PadV12)") (class "Default")
      (node (ref "U400") (pin "V12") (pinfunction "GPMC_CLK_/_GPIO2_1_V12") (pintype "passive"))
    )
    (net (code "75") (name "unconnected-(U400F-~{GPMC_BE1}_{slash}_GPIO1_28-PadU18)") (class "Default")
      (node (ref "U400") (pin "U18") (pinfunction "~{GPMC_BE1}_/_GPIO1_28_U18") (pintype "passive"))
    )
    (net (code "76") (name "unconnected-(U400F-~{GPMC_CS0}_{slash}_GPIO1_29-PadV6)") (class "Default")
      (node (ref "U400") (pin "V6") (pinfunction "~{GPMC_CS0}_/_GPIO1_29_V6") (pintype "passive"))
    )
    (net (code "77") (name "unconnected-(U702-NC-Pad1)") (class "Default")
      (node (ref "U702") (pin "1") (pinfunction "NC_1") (pintype "passive+no_connect"))
    )
    (net (code "78") (name "unconnected-(U703B-NC1-PadA1)") (class "Default")
      (node (ref "U703") (pin "A1") (pinfunction "NC1_A1") (pintype "passive+no_connect"))
    )
    (net (code "79") (name "unconnected-(U703B-NC2-PadA2)") (class "Default")
      (node (ref "U703") (pin "A2") (pinfunction "NC2_A2") (pintype "passive+no_connect"))
    )
    (net (code "80") (name "unconnected-(U703B-NC3-PadA8)") (class "Default")
      (node (ref "U703") (pin "A8") (pinfunction "NC3_A8") (pintype "passive+no_connect"))
    )
    (net (code "81") (name "unconnected-(U703B-NC4-PadA9)") (class "Default")
      (node (ref "U703") (pin "A9") (pinfunction "NC4_A9") (pintype "passive+no_connect"))
    )
    (net (code "82") (name "unconnected-(U703B-NC5-PadA10)") (class "Default")
      (node (ref "U703") (pin "A10") (pinfunction "NC5_A10") (pintype "passive+no_connect"))
    )
    (net (code "83") (name "unconnected-(U703B-NC6-PadA11)") (class "Default")
      (node (ref "U703") (pin "A11") (pinfunction "NC6_A11") (pintype "passive+no_connect"))
    )
    (net (code "84") (name "unconnected-(U703B-NC7-PadA12)") (class "Default")
      (node (ref "U703") (pin "A12") (pinfunction "NC7_A12") (pintype "passive+no_connect"))
    )
    (net (code "85") (name "unconnected-(U703B-NC8-PadA13)") (class "Default")
      (node (ref "U703") (pin "A13") (pinfunction "NC8_A13") (pintype "passive+no_connect"))
    )
    (net (code "86") (name "unconnected-(U703B-NC9-PadA14)") (class "Default")
      (node (ref "U703") (pin "A14") (pinfunction "NC9_A14") (pintype "passive+no_connect"))
    )
    (net (code "87") (name "unconnected-(U703B-NC10-PadB1)") (class "Default")
      (node (ref "U703") (pin "B1") (pinfunction "NC10_B1") (pintype "passive+no_connect"))
    )
    (net (code "88") (name "unconnected-(U703B-NC11-PadB7)") (class "Default")
      (node (ref "U703") (pin "B7") (pinfunction "NC11_B7") (pintype "passive+no_connect"))
    )
    (net (code "89") (name "unconnected-(U703B-NC12-PadB8)") (class "Default")
      (node (ref "U703") (pin "B8") (pinfunction "NC12_B8") (pintype "passive+no_connect"))
    )
    (net (code "90") (name "unconnected-(U703B-NC13-PadB9)") (class "Default")
      (node (ref "U703") (pin "B9") (pinfunction "NC13_B9") (pintype "passive+no_connect"))
    )
    (net (code "91") (name "unconnected-(U703B-NC14-PadB10)") (class "Default")
      (node (ref "U703") (pin "B10") (pinfunction "NC14_B10") (pintype "passive+no_connect"))
    )
    (net (code "92") (name "unconnected-(U703B-NC15-PadB11)") (class "Default")
      (node (ref "U703") (pin "B11") (pinfunction "NC15_B11") (pintype "passive+no_connect"))
    )
    (net (code "93") (name "unconnected-(U703B-NC16-PadB12)") (class "Default")
      (node (ref "U703") (pin "B12") (pinfunction "NC16_B12") (pintype "passive+no_connect"))
    )
    (net (code "94") (name "unconnected-(U703B-NC17-PadB13)") (class "Default")
      (node (ref "U703") (pin "B13") (pinfunction "NC17_B13") (pintype "passive+no_connect"))
    )
    (net (code "95") (name "unconnected-(U703B-NC18-PadB14)") (class "Default")
      (node (ref "U703") (pin "B14") (pinfunction "NC18_B14") (pintype "passive+no_connect"))
    )
    (net (code "96") (name "unconnected-(U703B-NC19-PadC1)") (class "Default")
      (node (ref "U703") (pin "C1") (pinfunction "NC19_C1") (pintype "passive+no_connect"))
    )
    (net (code "97") (name "unconnected-(U703B-NC20-PadC3)") (class "Default")
      (node (ref "U703") (pin "C3") (pinfunction "NC20_C3") (pintype "passive+no_connect"))
    )
    (net (code "98") (name "unconnected-(U703B-NC21-PadC5)") (class "Default")
      (node (ref "U703") (pin "C5") (pinfunction "NC21_C5") (pintype "passive+no_connect"))
    )
    (net (code "99") (name "unconnected-(U703B-NC22-PadC7)") (class "Default")
      (node (ref "U703") (pin "C7") (pinfunction "NC22_C7") (pintype "passive+no_connect"))
    )
    (net (code "100") (name "unconnected-(U703B-NC23-PadC8)") (class "Default")
      (node (ref "U703") (pin "C8") (pinfunction "NC23_C8") (pintype "passive+no_connect"))
    )
    (net (code "101") (name "unconnected-(U703B-NC24-PadC9)") (class "Default")
      (node (ref "U703") (pin "C9") (pinfunction "NC24_C9") (pintype "passive+no_connect"))
    )
    (net (code "102") (name "unconnected-(U703B-NC25-PadC10)") (class "Default")
      (node (ref "U703") (pin "C10") (pinfunction "NC25_C10") (pintype "passive+no_connect"))
    )
    (net (code "103") (name "unconnected-(U703B-NC26-PadC11)") (class "Default")
      (node (ref "U703") (pin "C11") (pinfunction "NC26_C11") (pintype "passive+no_connect"))
    )
    (net (code "104") (name "unconnected-(U703B-NC27-PadC12)") (class "Default")
      (node (ref "U703") (pin "C12") (pinfunction "NC27_C12") (pintype "passive+no_connect"))
    )
    (net (code "105") (name "unconnected-(U703B-NC28-PadC13)") (class "Default")
      (node (ref "U703") (pin "C13") (pinfunction "NC28_C13") (pintype "passive+no_connect"))
    )
    (net (code "106") (name "unconnected-(U703B-NC29-PadC14)") (class "Default")
      (node (ref "U703") (pin "C14") (pinfunction "NC29_C14") (pintype "passive+no_connect"))
    )
    (net (code "107") (name "unconnected-(U703B-NC30-PadD1)") (class "Default")
      (node (ref "U703") (pin "D1") (pinfunction "NC30_D1") (pintype "passive+no_connect"))
    )
    (net (code "108") (name "unconnected-(U703B-NC31-PadD2)") (class "Default")
      (node (ref "U703") (pin "D2") (pinfunction "NC31_D2") (pintype "passive+no_connect"))
    )
    (net (code "109") (name "unconnected-(U703B-NC32-PadD3)") (class "Default")
      (node (ref "U703") (pin "D3") (pinfunction "NC32_D3") (pintype "passive+no_connect"))
    )
    (net (code "110") (name "unconnected-(U703B-NC33-PadD4)") (class "Default")
      (node (ref "U703") (pin "D4") (pinfunction "NC33_D4") (pintype "passive+no_connect"))
    )
    (net (code "111") (name "unconnected-(U703B-NC34-PadD12)") (class "Default")
      (node (ref "U703") (pin "D12") (pinfunction "NC34_D12") (pintype "passive+no_connect"))
    )
    (net (code "112") (name "unconnected-(U703B-NC35-PadD13)") (class "Default")
      (node (ref "U703") (pin "D13") (pinfunction "NC35_D13") (pintype "passive+no_connect"))
    )
    (net (code "113") (name "unconnected-(U703B-NC36-PadD14)") (class "Default")
      (node (ref "U703") (pin "D14") (pinfunction "NC36_D14") (pintype "passive+no_connect"))
    )
    (net (code "114") (name "unconnected-(U703B-NC37-PadE1)") (class "Default")
      (node (ref "U703") (pin "E1") (pinfunction "NC37_E1") (pintype "passive+no_connect"))
    )
    (net (code "115") (name "unconnected-(U703B-NC38-PadE2)") (class "Default")
      (node (ref "U703") (pin "E2") (pinfunction "NC38_E2") (pintype "passive+no_connect"))
    )
    (net (code "116") (name "unconnected-(U703B-NC39-PadE3)") (class "Default")
      (node (ref "U703") (pin "E3") (pinfunction "NC39_E3") (pintype "passive+no_connect"))
    )
    (net (code "117") (name "unconnected-(U703B-NC40-PadE12)") (class "Default")
      (node (ref "U703") (pin "E12") (pinfunction "NC40_E12") (pintype "passive+no_connect"))
    )
    (net (code "118") (name "unconnected-(U703B-NC41-PadE13)") (class "Default")
      (node (ref "U703") (pin "E13") (pinfunction "NC41_E13") (pintype "passive+no_connect"))
    )
    (net (code "119") (name "unconnected-(U703B-NC42-PadE14)") (class "Default")
      (node (ref "U703") (pin "E14") (pinfunction "NC42_E14") (pintype "passive+no_connect"))
    )
    (net (code "120") (name "unconnected-(U703B-NC43-PadF1)") (class "Default")
      (node (ref "U703") (pin "F1") (pinfunction "NC43_F1") (pintype "passive+no_connect"))
    )
    (net (code "121") (name "unconnected-(U703B-NC44-PadF2)") (class "Default")
      (node (ref "U703") (pin "F2") (pinfunction "NC44_F2") (pintype "passive+no_connect"))
    )
    (net (code "122") (name "unconnected-(U703B-NC45-PadF3)") (class "Default")
      (node (ref "U703") (pin "F3") (pinfunction "NC45_F3") (pintype "passive+no_connect"))
    )
    (net (code "123") (name "unconnected-(U703B-NC46-PadF12)") (class "Default")
      (node (ref "U703") (pin "F12") (pinfunction "NC46_F12") (pintype "passive+no_connect"))
    )
    (net (code "124") (name "unconnected-(U703B-NC47-PadF13)") (class "Default")
      (node (ref "U703") (pin "F13") (pinfunction "NC47_F13") (pintype "passive+no_connect"))
    )
    (net (code "125") (name "unconnected-(U703B-NC48-PadF14)") (class "Default")
      (node (ref "U703") (pin "F14") (pinfunction "NC48_F14") (pintype "passive+no_connect"))
    )
    (net (code "126") (name "unconnected-(U703B-NC49-PadG1)") (class "Default")
      (node (ref "U703") (pin "G1") (pinfunction "NC49_G1") (pintype "passive+no_connect"))
    )
    (net (code "127") (name "unconnected-(U703B-NC50-PadG2)") (class "Default")
      (node (ref "U703") (pin "G2") (pinfunction "NC50_G2") (pintype "passive+no_connect"))
    )
    (net (code "128") (name "unconnected-(U703B-NC51-PadG3)") (class "Default")
      (node (ref "U703") (pin "G3") (pinfunction "NC51_G3") (pintype "passive+no_connect"))
    )
    (net (code "129") (name "unconnected-(U703B-NC52-PadG12)") (class "Default")
      (node (ref "U703") (pin "G12") (pinfunction "NC52_G12") (pintype "passive+no_connect"))
    )
    (net (code "130") (name "unconnected-(U703B-NC53-PadG13)") (class "Default")
      (node (ref "U703") (pin "G13") (pinfunction "NC53_G13") (pintype "passive+no_connect"))
    )
    (net (code "131") (name "unconnected-(U703B-NC54-PadG14)") (class "Default")
      (node (ref "U703") (pin "G14") (pinfunction "NC54_G14") (pintype "passive+no_connect"))
    )
    (net (code "132") (name "unconnected-(U703B-NC55-PadH1)") (class "Default")
      (node (ref "U703") (pin "H1") (pinfunction "NC55_H1") (pintype "passive+no_connect"))
    )
    (net (code "133") (name "unconnected-(U703B-NC56-PadH2)") (class "Default")
      (node (ref "U703") (pin "H2") (pinfunction "NC56_H2") (pintype "passive+no_connect"))
    )
    (net (code "134") (name "unconnected-(U703B-NC57-PadH3)") (class "Default")
      (node (ref "U703") (pin "H3") (pinfunction "NC57_H3") (pintype "passive+no_connect"))
    )
    (net (code "135") (name "unconnected-(U703B-NC58-PadH12)") (class "Default")
      (node (ref "U703") (pin "H12") (pinfunction "NC58_H12") (pintype "passive+no_connect"))
    )
    (net (code "136") (name "unconnected-(U703B-NC59-PadH13)") (class "Default")
      (node (ref "U703") (pin "H13") (pinfunction "NC59_H13") (pintype "passive+no_connect"))
    )
    (net (code "137") (name "unconnected-(U703B-NC60-PadH14)") (class "Default")
      (node (ref "U703") (pin "H14") (pinfunction "NC60_H14") (pintype "passive+no_connect"))
    )
    (net (code "138") (name "unconnected-(U703B-NC61-PadJ1)") (class "Default")
      (node (ref "U703") (pin "J1") (pinfunction "NC61_J1") (pintype "passive+no_connect"))
    )
    (net (code "139") (name "unconnected-(U703B-NC62-PadJ2)") (class "Default")
      (node (ref "U703") (pin "J2") (pinfunction "NC62_J2") (pintype "passive+no_connect"))
    )
    (net (code "140") (name "unconnected-(U703B-NC63-PadJ3)") (class "Default")
      (node (ref "U703") (pin "J3") (pinfunction "NC63_J3") (pintype "passive+no_connect"))
    )
    (net (code "141") (name "unconnected-(U703B-NC64-PadJ12)") (class "Default")
      (node (ref "U703") (pin "J12") (pinfunction "NC64_J12") (pintype "passive+no_connect"))
    )
    (net (code "142") (name "unconnected-(U703B-NC65-PadJ13)") (class "Default")
      (node (ref "U703") (pin "J13") (pinfunction "NC65_J13") (pintype "passive+no_connect"))
    )
    (net (code "143") (name "unconnected-(U703B-NC66-PadJ14)") (class "Default")
      (node (ref "U703") (pin "J14") (pinfunction "NC66_J14") (pintype "passive+no_connect"))
    )
    (net (code "144") (name "unconnected-(U703B-NC67-PadK1)") (class "Default")
      (node (ref "U703") (pin "K1") (pinfunction "NC67_K1") (pintype "passive+no_connect"))
    )
    (net (code "145") (name "unconnected-(U703B-NC68-PadK2)") (class "Default")
      (node (ref "U703") (pin "K2") (pinfunction "NC68_K2") (pintype "passive+no_connect"))
    )
    (net (code "146") (name "unconnected-(U703B-NC69-PadK3)") (class "Default")
      (node (ref "U703") (pin "K3") (pinfunction "NC69_K3") (pintype "passive+no_connect"))
    )
    (net (code "147") (name "unconnected-(U703B-NC70-PadK12)") (class "Default")
      (node (ref "U703") (pin "K12") (pinfunction "NC70_K12") (pintype "passive+no_connect"))
    )
    (net (code "148") (name "unconnected-(U703B-NC71-PadK13)") (class "Default")
      (node (ref "U703") (pin "K13") (pinfunction "NC71_K13") (pintype "passive+no_connect"))
    )
    (net (code "149") (name "unconnected-(U703B-NC72-PadK14)") (class "Default")
      (node (ref "U703") (pin "K14") (pinfunction "NC72_K14") (pintype "passive+no_connect"))
    )
    (net (code "150") (name "unconnected-(U703B-NC73-PadL1)") (class "Default")
      (node (ref "U703") (pin "L1") (pinfunction "NC73_L1") (pintype "passive+no_connect"))
    )
    (net (code "151") (name "unconnected-(U703B-NC74-PadL2)") (class "Default")
      (node (ref "U703") (pin "L2") (pinfunction "NC74_L2") (pintype "passive+no_connect"))
    )
    (net (code "152") (name "unconnected-(U703B-NC75-PadL3)") (class "Default")
      (node (ref "U703") (pin "L3") (pinfunction "NC75_L3") (pintype "passive+no_connect"))
    )
    (net (code "153") (name "unconnected-(U703B-NC76-PadL12)") (class "Default")
      (node (ref "U703") (pin "L12") (pinfunction "NC76_L12") (pintype "passive+no_connect"))
    )
    (net (code "154") (name "unconnected-(U703B-NC77-PadL13)") (class "Default")
      (node (ref "U703") (pin "L13") (pinfunction "NC77_L13") (pintype "passive+no_connect"))
    )
    (net (code "155") (name "unconnected-(U703B-NC78-PadL14)") (class "Default")
      (node (ref "U703") (pin "L14") (pinfunction "NC78_L14") (pintype "passive+no_connect"))
    )
    (net (code "156") (name "unconnected-(U703B-NC79-PadM1)") (class "Default")
      (node (ref "U703") (pin "M1") (pinfunction "NC79_M1") (pintype "passive+no_connect"))
    )
    (net (code "157") (name "unconnected-(U703B-NC80-PadM2)") (class "Default")
      (node (ref "U703") (pin "M2") (pinfunction "NC80_M2") (pintype "passive+no_connect"))
    )
    (net (code "158") (name "unconnected-(U703B-NC81-PadM3)") (class "Default")
      (node (ref "U703") (pin "M3") (pinfunction "NC81_M3") (pintype "passive+no_connect"))
    )
    (net (code "159") (name "unconnected-(U703B-NC82-PadM7)") (class "Default")
      (node (ref "U703") (pin "M7") (pinfunction "NC82_M7") (pintype "passive+no_connect"))
    )
    (net (code "160") (name "unconnected-(U703B-NC83-PadM8)") (class "Default")
      (node (ref "U703") (pin "M8") (pinfunction "NC83_M8") (pintype "passive+no_connect"))
    )
    (net (code "161") (name "unconnected-(U703B-NC84-PadM9)") (class "Default")
      (node (ref "U703") (pin "M9") (pinfunction "NC84_M9") (pintype "passive+no_connect"))
    )
    (net (code "162") (name "unconnected-(U703B-NC85-PadM10)") (class "Default")
      (node (ref "U703") (pin "M10") (pinfunction "NC85_M10") (pintype "passive+no_connect"))
    )
    (net (code "163") (name "unconnected-(U703B-NC86-PadM11)") (class "Default")
      (node (ref "U703") (pin "M11") (pinfunction "NC86_M11") (pintype "passive+no_connect"))
    )
    (net (code "164") (name "unconnected-(U703B-NC87-PadM12)") (class "Default")
      (node (ref "U703") (pin "M12") (pinfunction "NC87_M12") (pintype "passive+no_connect"))
    )
    (net (code "165") (name "unconnected-(U703B-NC88-PadM13)") (class "Default")
      (node (ref "U703") (pin "M13") (pinfunction "NC88_M13") (pintype "passive+no_connect"))
    )
    (net (code "166") (name "unconnected-(U703B-NC89-PadM14)") (class "Default")
      (node (ref "U703") (pin "M14") (pinfunction "NC89_M14") (pintype "passive+no_connect"))
    )
    (net (code "167") (name "unconnected-(U703B-NC90-PadN1)") (class "Default")
      (node (ref "U703") (pin "N1") (pinfunction "NC90_N1") (pintype "passive+no_connect"))
    )
    (net (code "168") (name "unconnected-(U703B-NC91-PadN3)") (class "Default")
      (node (ref "U703") (pin "N3") (pinfunction "NC91_N3") (pintype "passive+no_connect"))
    )
    (net (code "169") (name "unconnected-(U703B-NC92-PadN6)") (class "Default")
      (node (ref "U703") (pin "N6") (pinfunction "NC92_N6") (pintype "passive+no_connect"))
    )
    (net (code "170") (name "unconnected-(U703B-NC93-PadN7)") (class "Default")
      (node (ref "U703") (pin "N7") (pinfunction "NC93_N7") (pintype "passive+no_connect"))
    )
    (net (code "171") (name "unconnected-(U703B-NC94-PadN8)") (class "Default")
      (node (ref "U703") (pin "N8") (pinfunction "NC94_N8") (pintype "passive+no_connect"))
    )
    (net (code "172") (name "unconnected-(U703B-NC95-PadN9)") (class "Default")
      (node (ref "U703") (pin "N9") (pinfunction "NC95_N9") (pintype "passive+no_connect"))
    )
    (net (code "173") (name "unconnected-(U703B-NC96-PadN10)") (class "Default")
      (node (ref "U703") (pin "N10") (pinfunction "NC96_N10") (pintype "passive+no_connect"))
    )
    (net (code "174") (name "unconnected-(U703B-NC97-PadN11)") (class "Default")
      (node (ref "U703") (pin "N11") (pinfunction "NC97_N11") (pintype "passive+no_connect"))
    )
    (net (code "175") (name "unconnected-(U703B-NC98-PadN12)") (class "Default")
      (node (ref "U703") (pin "N12") (pinfunction "NC98_N12") (pintype "passive+no_connect"))
    )
    (net (code "176") (name "unconnected-(U703B-NC99-PadN13)") (class "Default")
      (node (ref "U703") (pin "N13") (pinfunction "NC99_N13") (pintype "passive+no_connect"))
    )
    (net (code "177") (name "unconnected-(U703B-NC100-PadN14)") (class "Default")
      (node (ref "U703") (pin "N14") (pinfunction "NC100_N14") (pintype "passive+no_connect"))
    )
    (net (code "178") (name "unconnected-(U703B-NC101-PadP1)") (class "Default")
      (node (ref "U703") (pin "P1") (pinfunction "NC101_P1") (pintype "passive+no_connect"))
    )
    (net (code "179") (name "unconnected-(U703B-NC102-PadP2)") (class "Default")
      (node (ref "U703") (pin "P2") (pinfunction "NC102_P2") (pintype "passive+no_connect"))
    )
    (net (code "180") (name "unconnected-(U703B-NC103-PadP7)") (class "Default")
      (node (ref "U703") (pin "P7") (pinfunction "NC103_P7") (pintype "passive+no_connect"))
    )
    (net (code "181") (name "unconnected-(U703B-NC104-PadP8)") (class "Default")
      (node (ref "U703") (pin "P8") (pinfunction "NC104_P8") (pintype "passive+no_connect"))
    )
    (net (code "182") (name "unconnected-(U703B-NC105-PadP9)") (class "Default")
      (node (ref "U703") (pin "P9") (pinfunction "NC105_P9") (pintype "passive+no_connect"))
    )
    (net (code "183") (name "unconnected-(U703B-NC106-PadP11)") (class "Default")
      (node (ref "U703") (pin "P11") (pinfunction "NC106_P11") (pintype "passive+no_connect"))
    )
    (net (code "184") (name "unconnected-(U703B-NC107-PadP12)") (class "Default")
      (node (ref "U703") (pin "P12") (pinfunction "NC107_P12") (pintype "passive+no_connect"))
    )
    (net (code "185") (name "unconnected-(U703B-NC108-PadP13)") (class "Default")
      (node (ref "U703") (pin "P13") (pinfunction "NC108_P13") (pintype "passive+no_connect"))
    )
    (net (code "186") (name "unconnected-(U703B-NC109-PadP14)") (class "Default")
      (node (ref "U703") (pin "P14") (pinfunction "NC109_P14") (pintype "passive+no_connect"))
    )
    (net (code "187") (name "unconnected-(U703B-RFU1-PadA7)") (class "Default")
      (node (ref "U703") (pin "A7") (pinfunction "RFU1_A7") (pintype "passive+no_connect"))
    )
    (net (code "188") (name "unconnected-(U703B-RFU2-PadE5)") (class "Default")
      (node (ref "U703") (pin "E5") (pinfunction "RFU2_E5") (pintype "passive+no_connect"))
    )
    (net (code "189") (name "unconnected-(U703B-RFU3-PadK6)") (class "Default")
      (node (ref "U703") (pin "K6") (pinfunction "RFU3_K6") (pintype "passive+no_connect"))
    )
    (net (code "190") (name "unconnected-(U703B-RFU4-PadK7)") (class "Default")
      (node (ref "U703") (pin "K7") (pinfunction "RFU4_K7") (pintype "passive+no_connect"))
    )
    (net (code "191") (name "unconnected-(U703B-VSF1-PadE8)") (class "Default")
      (node (ref "U703") (pin "E8") (pinfunction "VSF1_E8") (pintype "passive+no_connect"))
    )
    (net (code "192") (name "unconnected-(U703B-VSF2-PadE9)") (class "Default")
      (node (ref "U703") (pin "E9") (pinfunction "VSF2_E9") (pintype "passive+no_connect"))
    )
    (net (code "193") (name "unconnected-(U703B-VSF3-PadE10)") (class "Default")
      (node (ref "U703") (pin "E10") (pinfunction "VSF3_E10") (pintype "passive+no_connect"))
    )
    (net (code "194") (name "unconnected-(U703B-VSF4-PadF10)") (class "Default")
      (node (ref "U703") (pin "F10") (pinfunction "VSF4_F10") (pintype "passive+no_connect"))
    )
    (net (code "195") (name "unconnected-(U703B-VSF5-PadG10)") (class "Default")
      (node (ref "U703") (pin "G10") (pinfunction "VSF5_G10") (pintype "passive+no_connect"))
    )
    (net (code "196") (name "unconnected-(U703B-VSF6-PadK10)") (class "Default")
      (node (ref "U703") (pin "K10") (pinfunction "VSF6_K10") (pintype "passive+no_connect"))
    )
    (net (code "197") (name "unconnected-(U703B-VSF7-PadP10)") (class "Default")
      (node (ref "U703") (pin "P10") (pinfunction "VSF7_P10") (pintype "passive+no_connect"))
    )
  )
)
